# Cell_Temp_Comparator.net
KiCad netlist of a schematic drawn in Altium Designer
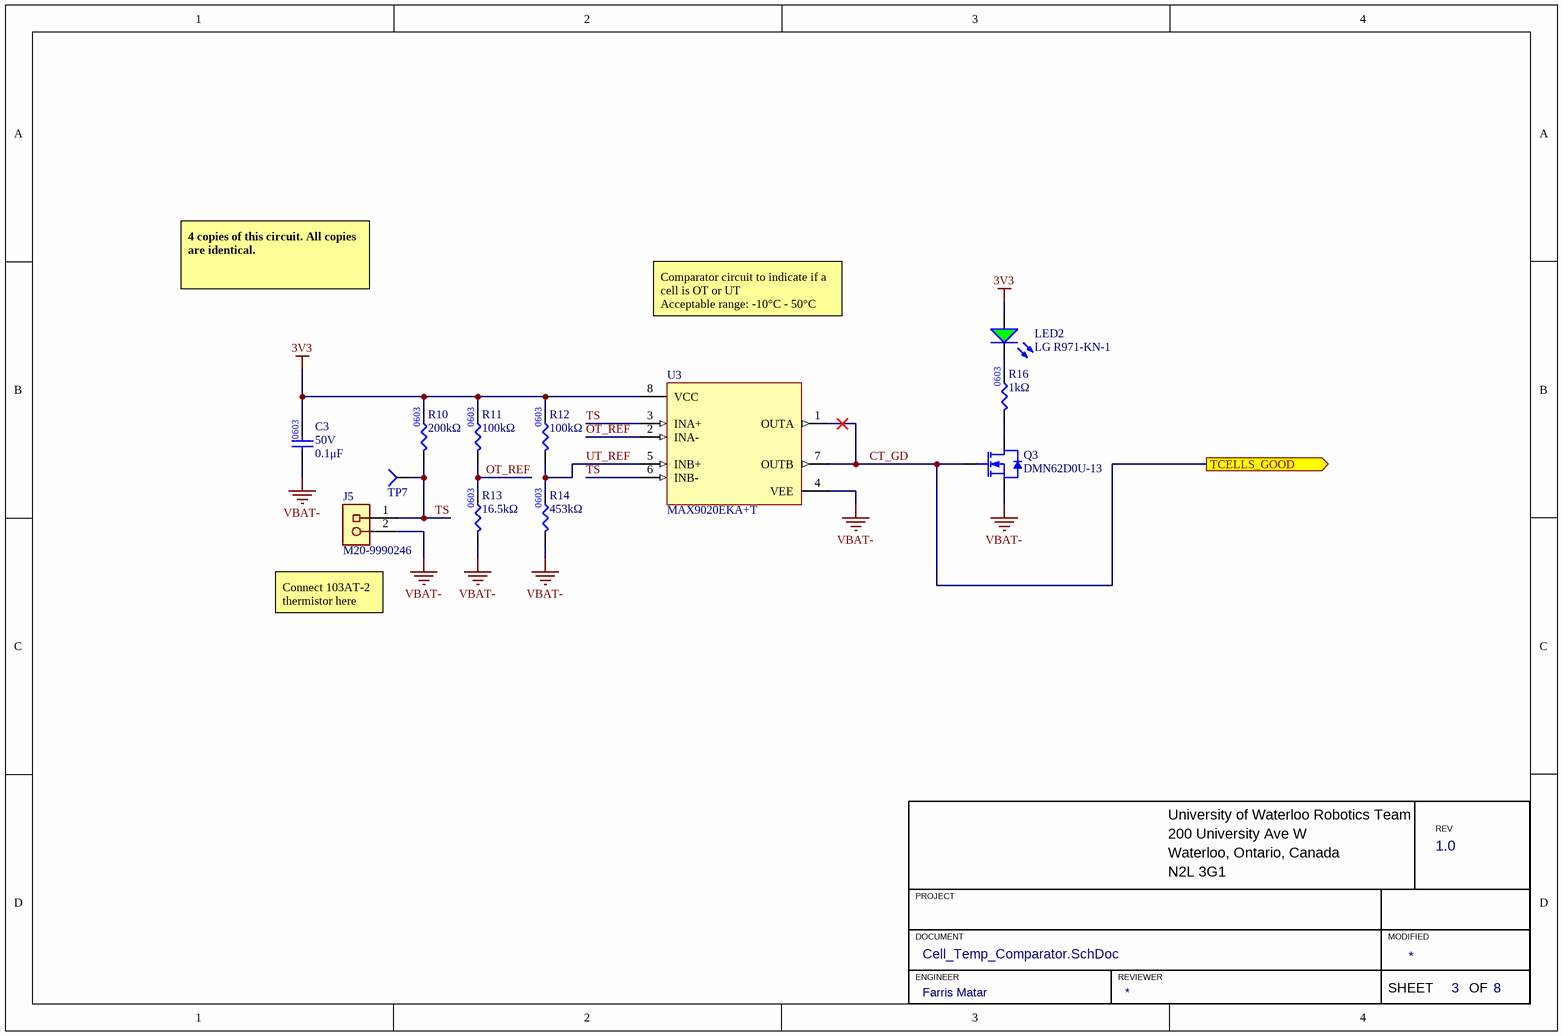
[diagram p0: Cell_Temp_Comparator.SchDoc]

(export (version "E")
  (design (tool "Eeschema 10.0.6"))
  (components
    (comp (ref "C3")
      (value "0.1μF")
      (footprint "CAP0603")
      (description "CAP CER 0.1UF 50V X7R 0603")
      (fields (field (name "VOLTAGE RATING") "50V") (field (name "Comment") "CAP_0.1uF_50V_0603"))
      (libsource (lib "UWRT_Schematic_Library_2020") (part "CAP_0.1uF_50V_0603"))
    )
    (comp (ref "J5")
      (value "HEADER 2x1")
      (footprint "HDR1X2")
      (description "HEADER 2X1")
      (fields (field (name "MANUFACTURER PART NUMBER 1") "M20-9990246"))
      (libsource (lib "Personal_Schematic_Library_2022") (part "HEADER 2x1"))
    )
    (comp (ref "LED2")
      (value "LED_GREEN")
      (footprint "LED_0805_GREEN")
      (description "LED GREEN DIFFUSED 0805 SMD")
      (fields (field (name "MANUFACTURER PART NUMBER 1") "LG R971-KN-1"))
      (libsource (lib "UWRT_Schematic_Library_2020") (part "LED_GREEN"))
    )
    (comp (ref "Q3")
      (value "NMOS_60V_380mA")
      (footprint "NMOS_SSOT-3")
      (description "MOSFET N-CH 60V 380MA SOT23")
      (fields (field (name "MANUFACTURER PART NUMBER 1") "DMN62D0U-13"))
      (libsource (lib "Personal_Schematic_Library_2022") (part "NMOS_60V_380mA"))
    )
    (comp (ref "R10")
      (value "200kΩ")
      (footprint "RES0603")
      (description "RES 200K OHM 1% 1/10W 0603")
      (fields (field (name "Comment") "RES_200kΩ_0603_1%"))
      (libsource (lib "Personal_Schematic_Library_2022") (part "RES_200kΩ_0603_1%"))
    )
    (comp (ref "R11")
      (value "100kΩ")
      (footprint "RES0603")
      (description "RES 100K OHM 1% 1/10W 0603")
      (fields (field (name "Comment") "RES_100kΩ_0603_1%"))
      (libsource (lib "Personal_Schematic_Library_2022") (part "RES_100kΩ_0603_1%"))
    )
    (comp (ref "R12")
      (value "100kΩ")
      (footprint "RES0603")
      (description "RES 100K OHM 1% 1/10W 0603")
      (fields (field (name "Comment") "RES_100kΩ_0603_1%"))
      (libsource (lib "Personal_Schematic_Library_2022") (part "RES_100kΩ_0603_1%"))
    )
    (comp (ref "R13")
      (value "16.5kΩ")
      (footprint "RES0603")
      (description "RES 16.5K OHM 1% 1/10W 0603")
      (fields (field (name "Comment") "RES_16.5kΩ_0603_1%"))
      (libsource (lib "Personal_Schematic_Library_2022") (part "RES_16.5kΩ_0603_1%"))
    )
    (comp (ref "R14")
      (value "453kΩ")
      (footprint "RES0603")
      (description "RES 453K OHM 1% 1/10W 0603")
      (fields (field (name "Comment") "RES_453kΩ_0603_1%"))
      (libsource (lib "Personal_Schematic_Library_2022") (part "RES_453kΩ_0603_1%"))
    )
    (comp (ref "R16")
      (value "1kΩ")
      (footprint "RES0603")
      (description "RES 1K OHM 1% 1/8W 0603")
      (fields (field (name "Comment") "RES_1kΩ_0603_1%"))
      (libsource (lib "Personal_Schematic_Library_2022") (part "RES_1kΩ_0603_1%"))
    )
    (comp (ref "TP7")
      (value "TESTPOINT_1MM_CIRCLE")
      (footprint "TESTPOINT_CIRCLE_1MM")
      (description "TESTPOINT 1MM CIRCLE")
      (libsource (lib "Personal_Schematic_Library_2022") (part "TESTPOINT_1MM_CIRCLE"))
    )
    (comp (ref "U3")
      (value "IC_COMPARATOR_MAX9020")
      (footprint "SOT23-8 MAXIM")
      (description "IC COMPARATOR DUAL SOT23-8")
      (fields (field (name "MANUFACTURER PART NUMBER 1") "MAX9020EKA+T"))
      (libsource (lib "Personal_Schematic_Library_2022") (part "IC_COMPARATOR_MAX9020"))
    )
  )
  (nets
    (net (code "1") (name "/CT_GD") (class "Default")
      (node (ref "Q3") (pin "1") (pinfunction "GATE_1") (pintype "passive"))
      (node (ref "U3") (pin "1") (pinfunction "OUTA_1") (pintype "output"))
      (node (ref "U3") (pin "7") (pinfunction "OUTB_7") (pintype "output"))
    )
    (net (code "2") (name "/OT_REF") (class "Default")
      (node (ref "R11") (pin "1") (pinfunction "1_1") (pintype "passive"))
      (node (ref "R13") (pin "2") (pinfunction "2_2") (pintype "passive"))
      (node (ref "U3") (pin "2") (pinfunction "INA-_2") (pintype "input"))
    )
    (net (code "3") (name "/TS") (class "Default")
      (node (ref "J5") (pin "1") (pinfunction "VCC_1") (pintype "passive"))
      (node (ref "R10") (pin "1") (pinfunction "1_1") (pintype "passive"))
      (node (ref "TP7") (pin "1") (pinfunction "=value_1") (pintype "passive"))
      (node (ref "U3") (pin "3") (pinfunction "INA+_3") (pintype "input"))
      (node (ref "U3") (pin "6") (pinfunction "INB-_6") (pintype "input"))
    )
    (net (code "4") (name "/UT_REF") (class "Default")
      (node (ref "R12") (pin "1") (pinfunction "1_1") (pintype "passive"))
      (node (ref "R14") (pin "2") (pinfunction "2_2") (pintype "passive"))
      (node (ref "U3") (pin "5") (pinfunction "INB+_5") (pintype "input"))
    )
    (net (code "5") (name "3V3") (class "Default")
      (node (ref "C3") (pin "2") (pinfunction "2_2") (pintype "passive"))
      (node (ref "LED2") (pin "1") (pinfunction "A_1") (pintype "passive"))
      (node (ref "R10") (pin "2") (pinfunction "2_2") (pintype "passive"))
      (node (ref "R11") (pin "2") (pinfunction "2_2") (pintype "passive"))
      (node (ref "R12") (pin "2") (pinfunction "2_2") (pintype "passive"))
      (node (ref "U3") (pin "8") (pinfunction "VCC_8") (pintype "power_in"))
    )
    (net (code "6") (name "Net-(LED2-K)") (class "Default")
      (node (ref "LED2") (pin "2") (pinfunction "K_2") (pintype "passive"))
      (node (ref "R16") (pin "2") (pinfunction "2_2") (pintype "passive"))
    )
    (net (code "7") (name "Net-(Q3-DRAIN)") (class "Default")
      (node (ref "Q3") (pin "3") (pinfunction "DRAIN_3") (pintype "passive"))
      (node (ref "R16") (pin "1") (pinfunction "1_1") (pintype "passive"))
    )
    (net (code "8") (name "VBAT-") (class "Default")
      (node (ref "C3") (pin "1") (pinfunction "1_1") (pintype "passive"))
      (node (ref "J5") (pin "2") (pinfunction "2_2") (pintype "passive"))
      (node (ref "Q3") (pin "2") (pinfunction "SOURCE_2") (pintype "passive"))
      (node (ref "R13") (pin "1") (pinfunction "1_1") (pintype "passive"))
      (node (ref "R14") (pin "1") (pinfunction "1_1") (pintype "passive"))
      (node (ref "U3") (pin "4") (pinfunction "VEE_4") (pintype "power_in"))
    )
  )
)
